# IMU.net
KiCad netlist of a schematic drawn in EAGLE
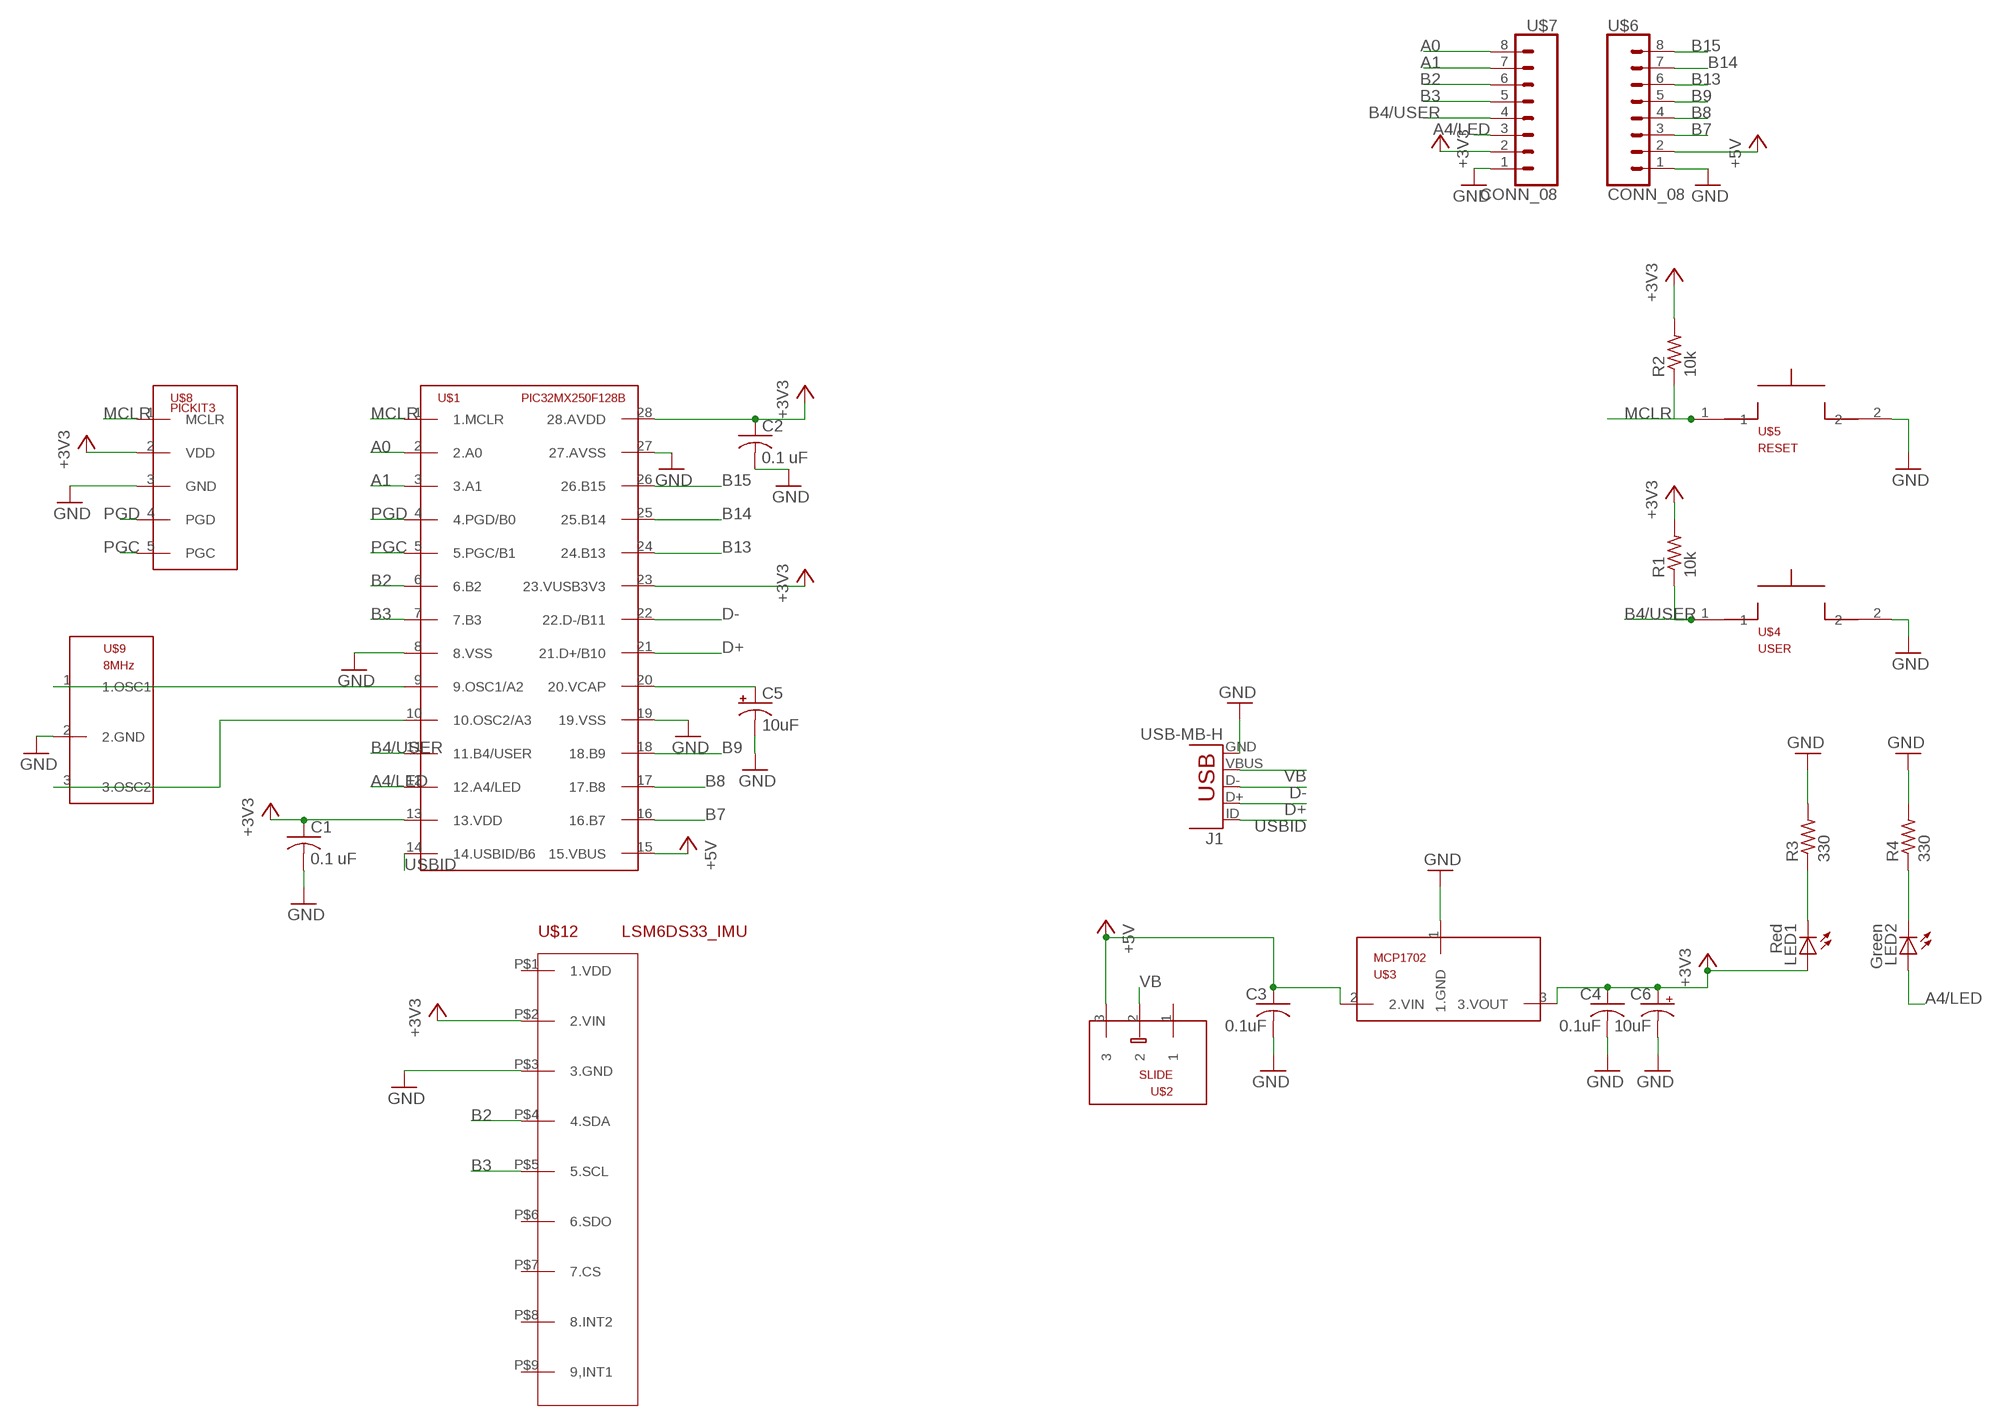
[diagram p0: schematic, sheet 1]

(export (version "E")
  (design (tool "Eeschema 10.0.6"))
  (components
    (comp (ref "C1")
      (value "0.1 uF")
      (footprint "eagle-import:C025-025X050")
      (libsource (lib "eagle-import") (part "C-US025-025X050"))
    )
    (comp (ref "C2")
      (value "0.1 uF")
      (footprint "eagle-import:C025-025X050")
      (libsource (lib "eagle-import") (part "C-US025-025X050"))
    )
    (comp (ref "C3")
      (value "0.1uF")
      (footprint "eagle-import:C025-025X050")
      (libsource (lib "eagle-import") (part "C-US025-025X050"))
    )
    (comp (ref "C4")
      (value "0.1uF")
      (footprint "eagle-import:C025-025X050")
      (libsource (lib "eagle-import") (part "C-US025-025X050"))
    )
    (comp (ref "C5")
      (value "10uF")
      (footprint "eagle-import:B45181B")
      (libsource (lib "eagle-import") (part "CPOL-USB45181B"))
    )
    (comp (ref "C6")
      (value "10uF")
      (footprint "eagle-import:B45181B")
      (libsource (lib "eagle-import") (part "CPOL-USB45181B"))
    )
    (comp (ref "J1")
      (value "USB-MB-H")
      (footprint "eagle-import:USB-MB-H")
      (libsource (lib "eagle-import") (part "USB-MB-H"))
    )
    (comp (ref "LED1")
      (value "Red")
      (footprint "eagle-import:LED3MM")
      (libsource (lib "eagle-import") (part "LED3MM"))
    )
    (comp (ref "LED2")
      (value "Green")
      (footprint "eagle-import:LED3MM")
      (libsource (lib "eagle-import") (part "LED3MM"))
    )
    (comp (ref "R1")
      (value "10k")
      (footprint "eagle-import:0207_10")
      (libsource (lib "eagle-import") (part "R-US_0207/10"))
    )
    (comp (ref "R2")
      (value "10k")
      (footprint "eagle-import:0207_10")
      (libsource (lib "eagle-import") (part "R-US_0207/10"))
    )
    (comp (ref "R3")
      (value "330")
      (footprint "eagle-import:0207_10")
      (libsource (lib "eagle-import") (part "R-US_0207/10"))
    )
    (comp (ref "R4")
      (value "330")
      (footprint "eagle-import:0207_10")
      (libsource (lib "eagle-import") (part "R-US_0207/10"))
    )
    (comp (ref "U$1")
      (value "PIC32MX250F128B")
      (footprint "eagle-import:DIL28-3")
      (libsource (lib "eagle-import") (part "PIC32MX250F128B"))
    )
    (comp (ref "U$2")
      (value "SLIDE")
      (footprint "eagle-import:SLIDE")
      (libsource (lib "eagle-import") (part "SLIDE"))
    )
    (comp (ref "U$3")
      (value "MCP1702")
      (footprint "eagle-import:TO92")
      (libsource (lib "eagle-import") (part "MCP1702"))
    )
    (comp (ref "U$4")
      (value "USER")
      (footprint "eagle-import:PB")
      (libsource (lib "eagle-import") (part "PB"))
    )
    (comp (ref "U$5")
      (value "RESET")
      (footprint "eagle-import:PB")
      (libsource (lib "eagle-import") (part "PB"))
    )
    (comp (ref "U$6")
      (value "CONN_08")
      (footprint "eagle-import:1X08")
      (libsource (lib "eagle-import") (part "CONN_08"))
    )
    (comp (ref "U$7")
      (value "CONN_08")
      (footprint "eagle-import:1X08")
      (libsource (lib "eagle-import") (part "CONN_08"))
    )
    (comp (ref "U$8")
      (value "PICKIT3")
      (footprint "eagle-import:1X05")
      (libsource (lib "eagle-import") (part "PICKIT3"))
    )
    (comp (ref "U$9")
      (value "8MHz")
      (footprint "eagle-import:OSC")
      (libsource (lib "eagle-import") (part "OSC"))
    )
    (comp (ref "U$12")
      (value "LSM6DS33_IMU")
      (footprint "eagle-import:LSM6DS33_IMU")
      (libsource (lib "eagle-import") (part "LSM6DS33_IMU"))
    )
  )
  (nets
    (net (code "1") (name "+3V3") (class "Default")
      (node (ref "C1") (pin "1") (pinfunction "1_1") (pintype "passive"))
      (node (ref "C2") (pin "1") (pinfunction "1_1") (pintype "passive"))
      (node (ref "C4") (pin "1") (pinfunction "1_1") (pintype "passive"))
      (node (ref "C6") (pin "+") (pinfunction "+_+") (pintype "passive"))
      (node (ref "LED1") (pin "A") (pinfunction "A_A") (pintype "passive"))
      (node (ref "R1") (pin "2") (pinfunction "2_2") (pintype "passive"))
      (node (ref "R2") (pin "2") (pinfunction "2_2") (pintype "passive"))
      (node (ref "U$1") (pin "13") (pinfunction "13.VDD_13") (pintype "bidirectional"))
      (node (ref "U$1") (pin "23") (pinfunction "23.VUSB3V3_23") (pintype "bidirectional"))
      (node (ref "U$1") (pin "28") (pinfunction "28.AVDD_28") (pintype "bidirectional"))
      (node (ref "U$12") (pin "P$2") (pinfunction "2.VIN_P$2") (pintype "bidirectional"))
      (node (ref "U$3") (pin "3") (pinfunction "3.VOUT_3") (pintype "bidirectional"))
      (node (ref "U$7") (pin "2") (pinfunction "2_2") (pintype "passive"))
      (node (ref "U$8") (pin "2") (pinfunction "VDD_2") (pintype "bidirectional"))
    )
    (net (code "2") (name "+5V") (class "Default")
      (node (ref "C3") (pin "1") (pinfunction "1_1") (pintype "passive"))
      (node (ref "U$1") (pin "15") (pinfunction "15.VBUS_15") (pintype "bidirectional"))
      (node (ref "U$2") (pin "3") (pinfunction "3_3") (pintype "bidirectional"))
      (node (ref "U$3") (pin "2") (pinfunction "2.VIN_2") (pintype "bidirectional"))
      (node (ref "U$6") (pin "2") (pinfunction "2_2") (pintype "passive"))
    )
    (net (code "3") (name "/A0") (class "Default")
      (node (ref "U$1") (pin "2") (pinfunction "2.A0_2") (pintype "bidirectional"))
      (node (ref "U$7") (pin "8") (pinfunction "8_8") (pintype "passive"))
    )
    (net (code "4") (name "/A1") (class "Default")
      (node (ref "U$1") (pin "3") (pinfunction "3.A1_3") (pintype "bidirectional"))
      (node (ref "U$7") (pin "7") (pinfunction "7_7") (pintype "passive"))
    )
    (net (code "5") (name "/A4{slash}LED") (class "Default")
      (node (ref "LED2") (pin "A") (pinfunction "A_A") (pintype "passive"))
      (node (ref "U$1") (pin "12") (pinfunction "12.A4/LED_12") (pintype "bidirectional"))
      (node (ref "U$7") (pin "3") (pinfunction "3_3") (pintype "passive"))
    )
    (net (code "6") (name "/B2") (class "Default")
      (node (ref "U$1") (pin "6") (pinfunction "6.B2_6") (pintype "bidirectional"))
      (node (ref "U$12") (pin "P$4") (pinfunction "4.SDA_P$4") (pintype "bidirectional"))
      (node (ref "U$7") (pin "6") (pinfunction "6_6") (pintype "passive"))
    )
    (net (code "7") (name "/B3") (class "Default")
      (node (ref "U$1") (pin "7") (pinfunction "7.B3_7") (pintype "bidirectional"))
      (node (ref "U$12") (pin "P$5") (pinfunction "5.SCL_P$5") (pintype "bidirectional"))
      (node (ref "U$7") (pin "5") (pinfunction "5_5") (pintype "passive"))
    )
    (net (code "8") (name "/B4{slash}USER") (class "Default")
      (node (ref "R1") (pin "1") (pinfunction "1_1") (pintype "passive"))
      (node (ref "U$1") (pin "11") (pinfunction "11.B4/USER_11") (pintype "bidirectional"))
      (node (ref "U$4") (pin "1") (pinfunction "1_1") (pintype "bidirectional"))
      (node (ref "U$7") (pin "4") (pinfunction "4_4") (pintype "passive"))
    )
    (net (code "9") (name "/B7") (class "Default")
      (node (ref "U$1") (pin "16") (pinfunction "16.B7_16") (pintype "bidirectional"))
      (node (ref "U$6") (pin "3") (pinfunction "3_3") (pintype "passive"))
    )
    (net (code "10") (name "/B8") (class "Default")
      (node (ref "U$1") (pin "17") (pinfunction "17.B8_17") (pintype "bidirectional"))
      (node (ref "U$6") (pin "4") (pinfunction "4_4") (pintype "passive"))
    )
    (net (code "11") (name "/B9") (class "Default")
      (node (ref "U$1") (pin "18") (pinfunction "18.B9_18") (pintype "bidirectional"))
      (node (ref "U$6") (pin "5") (pinfunction "5_5") (pintype "passive"))
    )
    (net (code "12") (name "/B13") (class "Default")
      (node (ref "U$1") (pin "24") (pinfunction "24.B13_24") (pintype "bidirectional"))
      (node (ref "U$6") (pin "6") (pinfunction "6_6") (pintype "passive"))
    )
    (net (code "13") (name "/B14") (class "Default")
      (node (ref "U$1") (pin "25") (pinfunction "25.B14_25") (pintype "bidirectional"))
      (node (ref "U$6") (pin "7") (pinfunction "7_7") (pintype "passive"))
    )
    (net (code "14") (name "/B15") (class "Default")
      (node (ref "U$1") (pin "26") (pinfunction "26.B15_26") (pintype "bidirectional"))
      (node (ref "U$6") (pin "8") (pinfunction "8_8") (pintype "passive"))
    )
    (net (code "15") (name "/D+") (class "Default")
      (node (ref "J1") (pin "D+") (pinfunction "D+_D+") (pintype "bidirectional"))
      (node (ref "U$1") (pin "21") (pinfunction "21.D+/B10_21") (pintype "bidirectional"))
    )
    (net (code "16") (name "/D-") (class "Default")
      (node (ref "J1") (pin "D-") (pinfunction "D-_D-") (pintype "bidirectional"))
      (node (ref "U$1") (pin "22") (pinfunction "22.D-/B11_22") (pintype "bidirectional"))
    )
    (net (code "17") (name "/MCLR") (class "Default")
      (node (ref "R2") (pin "1") (pinfunction "1_1") (pintype "passive"))
      (node (ref "U$1") (pin "1") (pinfunction "1.MCLR_1") (pintype "bidirectional"))
      (node (ref "U$5") (pin "1") (pinfunction "1_1") (pintype "bidirectional"))
      (node (ref "U$8") (pin "1") (pinfunction "MCLR_1") (pintype "bidirectional"))
    )
    (net (code "18") (name "/PGC") (class "Default")
      (node (ref "U$1") (pin "5") (pinfunction "5.PGC/B1_5") (pintype "bidirectional"))
      (node (ref "U$8") (pin "5") (pinfunction "PGC_5") (pintype "bidirectional"))
    )
    (net (code "19") (name "/PGD") (class "Default")
      (node (ref "U$1") (pin "4") (pinfunction "4.PGD/B0_4") (pintype "bidirectional"))
      (node (ref "U$8") (pin "4") (pinfunction "PGD_4") (pintype "bidirectional"))
    )
    (net (code "20") (name "/USBID") (class "Default")
      (node (ref "J1") (pin "ID") (pinfunction "ID_ID") (pintype "bidirectional"))
      (node (ref "U$1") (pin "14") (pinfunction "14.USBID/B6_14") (pintype "bidirectional"))
    )
    (net (code "21") (name "/VB") (class "Default")
      (node (ref "J1") (pin "VBUS") (pinfunction "VBUS_VBUS") (pintype "bidirectional"))
      (node (ref "U$2") (pin "2") (pinfunction "2_2") (pintype "bidirectional"))
    )
    (net (code "22") (name "GND") (class "Default")
      (node (ref "C1") (pin "2") (pinfunction "2_2") (pintype "passive"))
      (node (ref "C2") (pin "2") (pinfunction "2_2") (pintype "passive"))
      (node (ref "C3") (pin "2") (pinfunction "2_2") (pintype "passive"))
      (node (ref "C4") (pin "2") (pinfunction "2_2") (pintype "passive"))
      (node (ref "C5") (pin "-") (pinfunction "-_-") (pintype "passive"))
      (node (ref "C6") (pin "-") (pinfunction "-_-") (pintype "passive"))
      (node (ref "J1") (pin "GND") (pinfunction "GND_GND") (pintype "bidirectional"))
      (node (ref "R3") (pin "2") (pinfunction "2_2") (pintype "passive"))
      (node (ref "R4") (pin "2") (pinfunction "2_2") (pintype "passive"))
      (node (ref "U$1") (pin "19") (pinfunction "19.VSS_19") (pintype "bidirectional"))
      (node (ref "U$1") (pin "27") (pinfunction "27.AVSS_27") (pintype "bidirectional"))
      (node (ref "U$1") (pin "8") (pinfunction "8.VSS_8") (pintype "bidirectional"))
      (node (ref "U$12") (pin "P$3") (pinfunction "3.GND_P$3") (pintype "bidirectional"))
      (node (ref "U$3") (pin "1") (pinfunction "1.GND_1") (pintype "bidirectional"))
      (node (ref "U$4") (pin "2") (pinfunction "2_2") (pintype "bidirectional"))
      (node (ref "U$5") (pin "2") (pinfunction "2_2") (pintype "bidirectional"))
      (node (ref "U$6") (pin "1") (pinfunction "1_1") (pintype "passive"))
      (node (ref "U$7") (pin "1") (pinfunction "1_1") (pintype "passive"))
      (node (ref "U$8") (pin "3") (pinfunction "GND_3") (pintype "bidirectional"))
      (node (ref "U$9") (pin "2") (pinfunction "2.GND_2") (pintype "bidirectional"))
    )
    (net (code "23") (name "Net-(LED1-C)") (class "Default")
      (node (ref "LED1") (pin "K") (pinfunction "C_K") (pintype "passive"))
      (node (ref "R3") (pin "1") (pinfunction "1_1") (pintype "passive"))
    )
    (net (code "24") (name "Net-(LED2-C)") (class "Default")
      (node (ref "LED2") (pin "K") (pinfunction "C_K") (pintype "passive"))
      (node (ref "R4") (pin "1") (pinfunction "1_1") (pintype "passive"))
    )
    (net (code "25") (name "Net-(U$1-9.OSC1{slash}A2)") (class "Default")
      (node (ref "U$1") (pin "9") (pinfunction "9.OSC1/A2_9") (pintype "bidirectional"))
      (node (ref "U$9") (pin "1") (pinfunction "1.OSC1_1") (pintype "bidirectional"))
    )
    (net (code "26") (name "Net-(U$1-10.OSC2{slash}A3)") (class "Default")
      (node (ref "U$1") (pin "10") (pinfunction "10.OSC2/A3_10") (pintype "bidirectional"))
      (node (ref "U$9") (pin "3") (pinfunction "3.OSC2_3") (pintype "bidirectional"))
    )
    (net (code "27") (name "Net-(U$1-20.VCAP)") (class "Default")
      (node (ref "C5") (pin "+") (pinfunction "+_+") (pintype "passive"))
      (node (ref "U$1") (pin "20") (pinfunction "20.VCAP_20") (pintype "bidirectional"))
    )
    (net (code "28") (name "unconnected-(U$2-Pad1)") (class "Default")
      (node (ref "U$2") (pin "1") (pinfunction "1_1") (pintype "bidirectional"))
    )
    (net (code "29") (name "unconnected-(U$12-1.VDD-PadP$1)") (class "Default")
      (node (ref "U$12") (pin "P$1") (pinfunction "1.VDD_P$1") (pintype "bidirectional"))
    )
    (net (code "30") (name "unconnected-(U$12-6.SDO-PadP$6)") (class "Default")
      (node (ref "U$12") (pin "P$6") (pinfunction "6.SDO_P$6") (pintype "bidirectional"))
    )
    (net (code "31") (name "unconnected-(U$12-7.CS-PadP$7)") (class "Default")
      (node (ref "U$12") (pin "P$7") (pinfunction "7.CS_P$7") (pintype "bidirectional"))
    )
    (net (code "32") (name "unconnected-(U$12-8.INT2-PadP$8)") (class "Default")
      (node (ref "U$12") (pin "P$8") (pinfunction "8.INT2_P$8") (pintype "bidirectional"))
    )
    (net (code "33") (name "unconnected-(U$12-9,INT1-PadP$9)") (class "Default")
      (node (ref "U$12") (pin "P$9") (pinfunction "9,INT1_P$9") (pintype "bidirectional"))
    )
  )
)
